# Microcontroller.net
KiCad netlist of a schematic drawn in Altium Designer
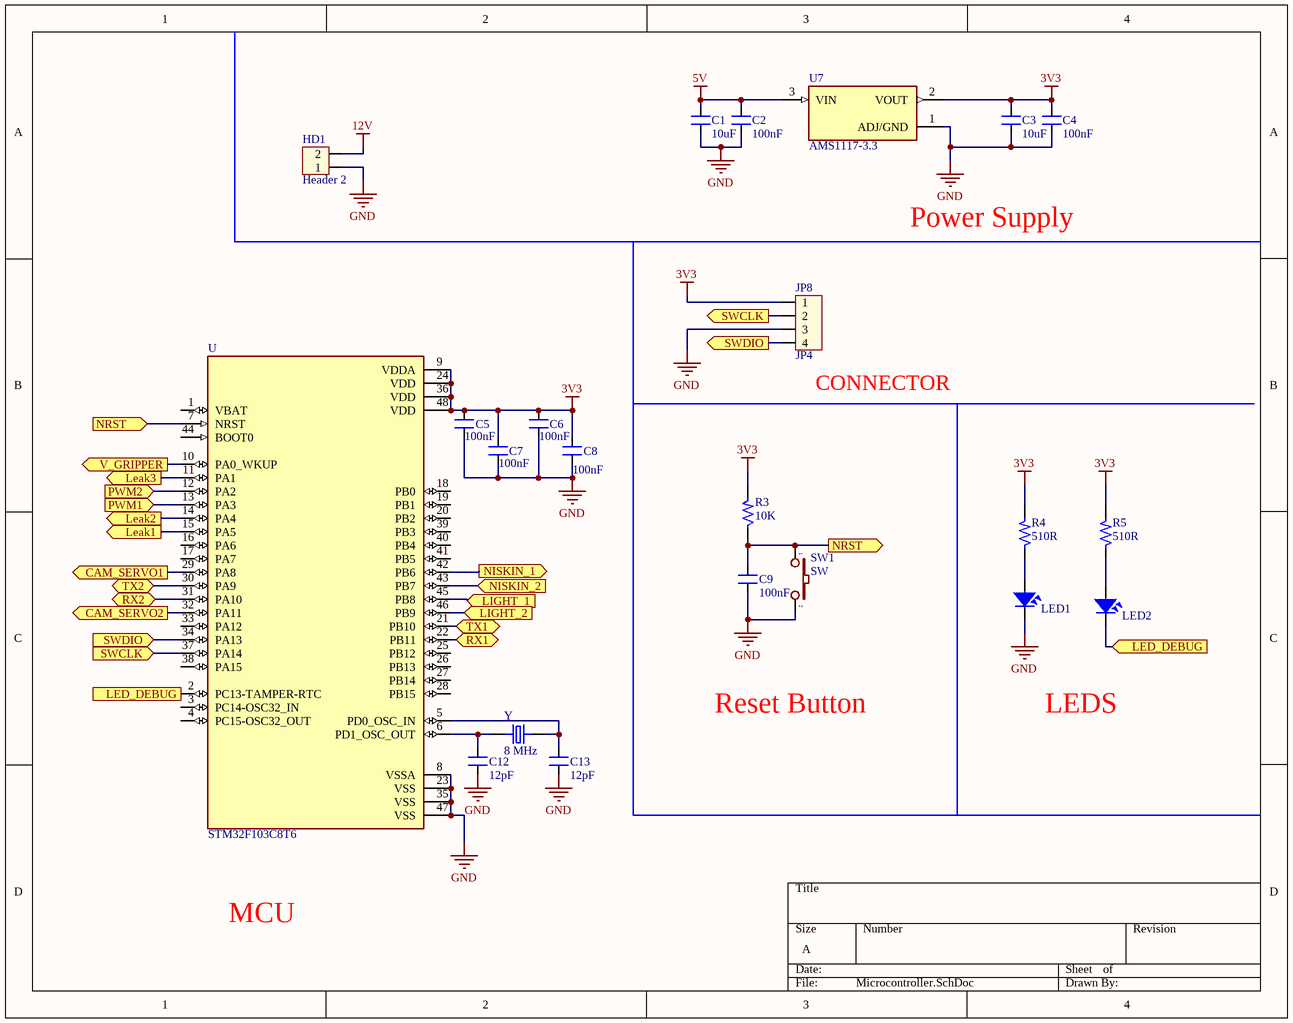
[diagram p0: Microcontroller.SchDoc]

(export (version "E")
  (design (tool "Eeschema 10.0.6"))
  (components
    (comp (ref "C1")
      (value "10uF")
      (footprint "SM-0805")
      (description "Cap SMD")
      (libsource (lib "syhaunguyen") (part "CM"))
    )
    (comp (ref "C2")
      (value "100nF")
      (footprint "SM-0805")
      (description "Cap SMD")
      (libsource (lib "syhaunguyen") (part "CM"))
    )
    (comp (ref "C3")
      (value "10uF")
      (footprint "SM-0805")
      (description "Cap SMD")
      (libsource (lib "syhaunguyen") (part "CM"))
    )
    (comp (ref "C4")
      (value "100nF")
      (footprint "SM-0805")
      (description "Cap SMD")
      (libsource (lib "syhaunguyen") (part "CM"))
    )
    (comp (ref "C5")
      (value "100nF")
      (footprint "SM-0805")
      (description "Cap SMD")
      (libsource (lib "echipkool-com-library") (part "CM"))
    )
    (comp (ref "C6")
      (value "100nF")
      (footprint "SM-0805")
      (description "Cap SMD")
      (libsource (lib "echipkool-com-library") (part "CM"))
    )
    (comp (ref "C7")
      (value "100nF")
      (footprint "SM-0805")
      (description "Cap SMD")
      (libsource (lib "echipkool-com-library") (part "CM"))
    )
    (comp (ref "C8")
      (value "100nF")
      (footprint "SM-0805")
      (description "Cap SMD")
      (libsource (lib "echipkool-com-library") (part "CM"))
    )
    (comp (ref "C9")
      (value "100nF")
      (footprint "SM-0805")
      (description "Cap SMD")
      (libsource (lib "echipkool-com-library") (part "CM"))
    )
    (comp (ref "C12")
      (value "12pF")
      (footprint "SM-0805")
      (description "Cap SMD")
      (libsource (lib "syhaunguyen") (part "CM"))
    )
    (comp (ref "C13")
      (value "12pF")
      (footprint "SM-0805")
      (description "Cap SMD")
      (libsource (lib "syhaunguyen") (part "CM"))
    )
    (comp (ref "HD1")
      (value "Header 2")
      (footprint "HED2")
      (description "Header 2 (Green)")
      (libsource (lib "syhaunguyen") (part "Hed2"))
    )
    (comp (ref "JP8")
      (value "JP4")
      (footprint "JP4")
      (description "Connector 4")
      (libsource (lib "syhaunguyen") (part "Con4"))
    )
    (comp (ref "LED1")
      (value "LED SMD")
      (footprint "SM-LED-0805-Blue")
      (libsource (lib "echipkool-com-library") (part "LED-SMD-0805"))
    )
    (comp (ref "LED2")
      (value "LED SMD")
      (footprint "SM-LED-0805-Yellow")
      (libsource (lib "echipkool-com-library") (part "LED-SMD-0805"))
    )
    (comp (ref "R3")
      (value "10K")
      (footprint "SM-RES-0805")
      (description "Resistor 1/4W")
      (libsource (lib "echipkool-com-library") (part "R"))
    )
    (comp (ref "R4")
      (value "510R")
      (footprint "SM-RES-0805")
      (description "Resistor 1/4W")
      (libsource (lib "syhaunguyen") (part "R"))
    )
    (comp (ref "R5")
      (value "510R")
      (footprint "SM-RES-0805")
      (description "Resistor 1/4W")
      (libsource (lib "syhaunguyen") (part "R"))
    )
    (comp (ref "SW1")
      (value "SW")
      (footprint "SW2")
      (description "Switch button 2 pin")
      (libsource (lib "echipkool-com-library") (part "SW2"))
    )
    (comp (ref "U")
      (value "STM32F103C8T6")
      (footprint "QFP50P900X900X160-48N")
      (description "ARMÂ® CortexÂ®-M3 STM32F1 Microcontroller IC 32-Bit 72MHz 64KB _64K x 8_ FLASH")
      (fields (field (name "MF") "STMicroelectronics"))
      (libsource (lib "STM32F103C8T6") (part "STM32F103C8T6"))
    )
    (comp (ref "U7")
      (value "AMS1117-3.3")
      (footprint "SOT229P700X180-4N")
      (description "Sot223/Pkg 1-Amp 3.3-Volt Low Drop Out Voltage Regulatator")
      (fields (field (name "MF") "Advanced Monolithic Systems"))
      (libsource (lib "AMS1117-3.3") (part "AMS1117-3.3"))
    )
    (comp (ref "Y")
      (value "8 MHz")
      (footprint "XTAL_ECS-120.003-18-5P-TR")
      (fields (field (name "MF") "ECS International") (field (name "MP") "ECS-120.003-18-5P-TR"))
      (libsource (lib "Crystal_SMD") (part "ECS-120.003-18-5P-TR"))
    )
  )
  (nets
    (net (code "1") (name "/CAM_SERVO1") (class "Default")
      (node (ref "U") (pin "29") (pinfunction "PA8_29") (pintype "bidirectional"))
    )
    (net (code "2") (name "/CAM_SERVO2") (class "Default")
      (node (ref "U") (pin "32") (pinfunction "PA11_32") (pintype "bidirectional"))
    )
    (net (code "3") (name "/LED_DEBUG") (class "Default")
      (node (ref "LED2") (pin "2") (pinfunction "2_2") (pintype "passive"))
      (node (ref "U") (pin "2") (pinfunction "PC13-TAMPER-RTC_2") (pintype "bidirectional"))
    )
    (net (code "4") (name "/LIGHT_1") (class "Default")
      (node (ref "U") (pin "45") (pinfunction "PB8_45") (pintype "bidirectional"))
    )
    (net (code "5") (name "/LIGHT_2") (class "Default")
      (node (ref "U") (pin "46") (pinfunction "PB9_46") (pintype "bidirectional"))
    )
    (net (code "6") (name "/Leak1") (class "Default")
      (node (ref "U") (pin "15") (pinfunction "PA5_15") (pintype "bidirectional"))
    )
    (net (code "7") (name "/Leak2") (class "Default")
      (node (ref "U") (pin "14") (pinfunction "PA4_14") (pintype "bidirectional"))
    )
    (net (code "8") (name "/Leak3") (class "Default")
      (node (ref "U") (pin "11") (pinfunction "PA1_11") (pintype "bidirectional"))
    )
    (net (code "9") (name "/NISKIN_1") (class "Default")
      (node (ref "U") (pin "42") (pinfunction "PB6_42") (pintype "bidirectional"))
    )
    (net (code "10") (name "/NISKIN_2") (class "Default")
      (node (ref "U") (pin "43") (pinfunction "PB7_43") (pintype "bidirectional"))
    )
    (net (code "11") (name "/NRST") (class "Default")
      (node (ref "C9") (pin "2") (pinfunction "2_2") (pintype "passive"))
      (node (ref "R3") (pin "1") (pinfunction "1_1") (pintype "passive"))
      (node (ref "SW1") (pin "1") (pinfunction "1_1") (pintype "passive"))
      (node (ref "U") (pin "7") (pinfunction "NRST_7") (pintype "input"))
    )
    (net (code "12") (name "/PWM1") (class "Default")
      (node (ref "U") (pin "13") (pinfunction "PA3_13") (pintype "bidirectional"))
    )
    (net (code "13") (name "/PWM2") (class "Default")
      (node (ref "U") (pin "12") (pinfunction "PA2_12") (pintype "bidirectional"))
    )
    (net (code "14") (name "/RX1") (class "Default")
      (node (ref "U") (pin "22") (pinfunction "PB11_22") (pintype "bidirectional"))
    )
    (net (code "15") (name "/RX2") (class "Default")
      (node (ref "U") (pin "31") (pinfunction "PA10_31") (pintype "bidirectional"))
    )
    (net (code "16") (name "/SWCLK") (class "Default")
      (node (ref "JP8") (pin "2") (pinfunction "2_2") (pintype "passive"))
      (node (ref "U") (pin "37") (pinfunction "PA14_37") (pintype "bidirectional"))
    )
    (net (code "17") (name "/SWDIO") (class "Default")
      (node (ref "JP8") (pin "4") (pinfunction "4_4") (pintype "passive"))
      (node (ref "U") (pin "34") (pinfunction "PA13_34") (pintype "bidirectional"))
    )
    (net (code "18") (name "/TX1") (class "Default")
      (node (ref "U") (pin "21") (pinfunction "PB10_21") (pintype "bidirectional"))
    )
    (net (code "19") (name "/TX2") (class "Default")
      (node (ref "U") (pin "30") (pinfunction "PA9_30") (pintype "bidirectional"))
    )
    (net (code "20") (name "/V_GRIPPER") (class "Default")
      (node (ref "U") (pin "10") (pinfunction "PA0_WKUP_10") (pintype "bidirectional"))
    )
    (net (code "21") (name "3V3") (class "Default")
      (node (ref "C3") (pin "2") (pinfunction "2_2") (pintype "passive"))
      (node (ref "C4") (pin "2") (pinfunction "2_2") (pintype "passive"))
      (node (ref "C5") (pin "2") (pinfunction "2_2") (pintype "passive"))
      (node (ref "C6") (pin "2") (pinfunction "2_2") (pintype "passive"))
      (node (ref "C7") (pin "2") (pinfunction "2_2") (pintype "passive"))
      (node (ref "C8") (pin "2") (pinfunction "2_2") (pintype "passive"))
      (node (ref "JP8") (pin "1") (pinfunction "1_1") (pintype "passive"))
      (node (ref "R3") (pin "2") (pinfunction "2_2") (pintype "passive"))
      (node (ref "R4") (pin "2") (pinfunction "2_2") (pintype "passive"))
      (node (ref "R5") (pin "2") (pinfunction "2_2") (pintype "passive"))
      (node (ref "U") (pin "24") (pinfunction "VDD_24") (pintype "power_in"))
      (node (ref "U") (pin "36") (pinfunction "VDD_36") (pintype "power_in"))
      (node (ref "U") (pin "48") (pinfunction "VDD_48") (pintype "power_in"))
      (node (ref "U") (pin "9") (pinfunction "VDDA_9") (pintype "power_in"))
      (node (ref "U7") (pin "2") (pinfunction "VOUT_2") (pintype "output"))
    )
    (net (code "22") (name "5V") (class "Default")
      (node (ref "C1") (pin "2") (pinfunction "2_2") (pintype "passive"))
      (node (ref "C2") (pin "2") (pinfunction "2_2") (pintype "passive"))
      (node (ref "U7") (pin "3") (pinfunction "VIN_3") (pintype "input"))
    )
    (net (code "23") (name "12V") (class "Default")
      (node (ref "HD1") (pin "2") (pinfunction "2_2") (pintype "passive"))
    )
    (net (code "24") (name "GND") (class "Default")
      (node (ref "C1") (pin "1") (pinfunction "1_1") (pintype "passive"))
      (node (ref "C12") (pin "1") (pinfunction "1_1") (pintype "passive"))
      (node (ref "C13") (pin "1") (pinfunction "1_1") (pintype "passive"))
      (node (ref "C2") (pin "1") (pinfunction "1_1") (pintype "passive"))
      (node (ref "C3") (pin "1") (pinfunction "1_1") (pintype "passive"))
      (node (ref "C4") (pin "1") (pinfunction "1_1") (pintype "passive"))
      (node (ref "C5") (pin "1") (pinfunction "1_1") (pintype "passive"))
      (node (ref "C6") (pin "1") (pinfunction "1_1") (pintype "passive"))
      (node (ref "C7") (pin "1") (pinfunction "1_1") (pintype "passive"))
      (node (ref "C8") (pin "1") (pinfunction "1_1") (pintype "passive"))
      (node (ref "C9") (pin "1") (pinfunction "1_1") (pintype "passive"))
      (node (ref "HD1") (pin "1") (pinfunction "1_1") (pintype "passive"))
      (node (ref "JP8") (pin "3") (pinfunction "3_3") (pintype "passive"))
      (node (ref "LED1") (pin "2") (pinfunction "2_2") (pintype "passive"))
      (node (ref "SW1") (pin "2") (pinfunction "2_2") (pintype "passive"))
      (node (ref "U") (pin "23") (pinfunction "VSS_23") (pintype "power_in"))
      (node (ref "U") (pin "35") (pinfunction "VSS_35") (pintype "power_in"))
      (node (ref "U") (pin "47") (pinfunction "VSS_47") (pintype "power_in"))
      (node (ref "U") (pin "8") (pinfunction "VSSA_8") (pintype "power_in"))
      (node (ref "U7") (pin "1") (pinfunction "ADJ/GND_1") (pintype "power_in"))
    )
    (net (code "25") (name "Net-(LED1-Pad1)") (class "Default")
      (node (ref "LED1") (pin "1") (pinfunction "1_1") (pintype "passive"))
      (node (ref "R4") (pin "1") (pinfunction "1_1") (pintype "passive"))
    )
    (net (code "26") (name "Net-(LED2-Pad1)") (class "Default")
      (node (ref "LED2") (pin "1") (pinfunction "1_1") (pintype "passive"))
      (node (ref "R5") (pin "1") (pinfunction "1_1") (pintype "passive"))
    )
    (net (code "27") (name "Net-(U-PD0_OSC_IN)") (class "Default")
      (node (ref "C13") (pin "2") (pinfunction "2_2") (pintype "passive"))
      (node (ref "U") (pin "5") (pinfunction "PD0_OSC_IN_5") (pintype "bidirectional"))
      (node (ref "Y") (pin "2") (pinfunction "2_2") (pintype "passive"))
    )
    (net (code "28") (name "Net-(U-PD1_OSC_OUT)") (class "Default")
      (node (ref "C12") (pin "2") (pinfunction "2_2") (pintype "passive"))
      (node (ref "U") (pin "6") (pinfunction "PD1_OSC_OUT_6") (pintype "bidirectional"))
      (node (ref "Y") (pin "1") (pinfunction "1_1") (pintype "passive"))
    )
    (net (code "29") (name "unconnected-(U-BOOT0-Pad44)") (class "Default")
      (node (ref "U") (pin "44") (pinfunction "BOOT0_44") (pintype "input"))
    )
    (net (code "30") (name "unconnected-(U-PA6-Pad16)") (class "Default")
      (node (ref "U") (pin "16") (pinfunction "PA6_16") (pintype "bidirectional"))
    )
    (net (code "31") (name "unconnected-(U-PA7-Pad17)") (class "Default")
      (node (ref "U") (pin "17") (pinfunction "PA7_17") (pintype "bidirectional"))
    )
    (net (code "32") (name "unconnected-(U-PA12-Pad33)") (class "Default")
      (node (ref "U") (pin "33") (pinfunction "PA12_33") (pintype "bidirectional"))
    )
    (net (code "33") (name "unconnected-(U-PA15-Pad38)") (class "Default")
      (node (ref "U") (pin "38") (pinfunction "PA15_38") (pintype "bidirectional"))
    )
    (net (code "34") (name "unconnected-(U-PB0-Pad18)") (class "Default")
      (node (ref "U") (pin "18") (pinfunction "PB0_18") (pintype "bidirectional"))
    )
    (net (code "35") (name "unconnected-(U-PB1-Pad19)") (class "Default")
      (node (ref "U") (pin "19") (pinfunction "PB1_19") (pintype "bidirectional"))
    )
    (net (code "36") (name "unconnected-(U-PB2-Pad20)") (class "Default")
      (node (ref "U") (pin "20") (pinfunction "PB2_20") (pintype "bidirectional"))
    )
    (net (code "37") (name "unconnected-(U-PB3-Pad39)") (class "Default")
      (node (ref "U") (pin "39") (pinfunction "PB3_39") (pintype "bidirectional"))
    )
    (net (code "38") (name "unconnected-(U-PB4-Pad40)") (class "Default")
      (node (ref "U") (pin "40") (pinfunction "PB4_40") (pintype "bidirectional"))
    )
    (net (code "39") (name "unconnected-(U-PB5-Pad41)") (class "Default")
      (node (ref "U") (pin "41") (pinfunction "PB5_41") (pintype "bidirectional"))
    )
    (net (code "40") (name "unconnected-(U-PB12-Pad25)") (class "Default")
      (node (ref "U") (pin "25") (pinfunction "PB12_25") (pintype "bidirectional"))
    )
    (net (code "41") (name "unconnected-(U-PB13-Pad26)") (class "Default")
      (node (ref "U") (pin "26") (pinfunction "PB13_26") (pintype "bidirectional"))
    )
    (net (code "42") (name "unconnected-(U-PB14-Pad27)") (class "Default")
      (node (ref "U") (pin "27") (pinfunction "PB14_27") (pintype "bidirectional"))
    )
    (net (code "43") (name "unconnected-(U-PB15-Pad28)") (class "Default")
      (node (ref "U") (pin "28") (pinfunction "PB15_28") (pintype "bidirectional"))
    )
    (net (code "44") (name "unconnected-(U-PC14-OSC32_IN-Pad3)") (class "Default")
      (node (ref "U") (pin "3") (pinfunction "PC14-OSC32_IN_3") (pintype "bidirectional"))
    )
    (net (code "45") (name "unconnected-(U-PC15-OSC32_OUT-Pad4)") (class "Default")
      (node (ref "U") (pin "4") (pinfunction "PC15-OSC32_OUT_4") (pintype "bidirectional"))
    )
    (net (code "46") (name "unconnected-(U-VBAT-Pad1)") (class "Default")
      (node (ref "U") (pin "1") (pinfunction "VBAT_1") (pintype "bidirectional"))
    )
  )
)
